# RAM.net
KiCad netlist of a schematic drawn in EAGLE
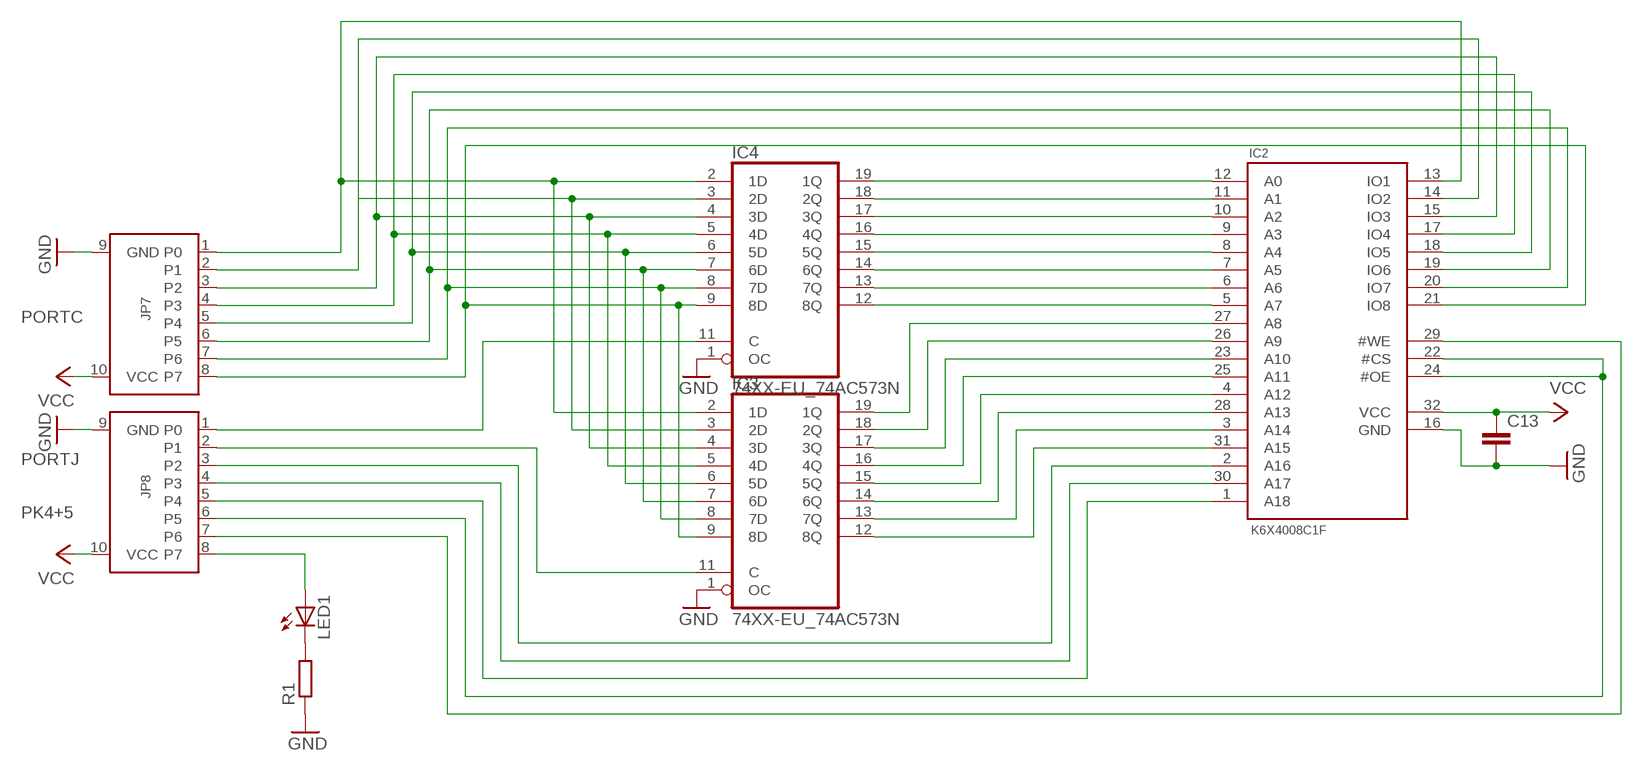
[diagram p0: schematic, sheet 1]

(export (version "E")
  (design (tool "Eeschema 10.0.6"))
  (components
    (comp (ref "C13")
      (value "C-EU050-035X075")
      (footprint "eagle-import:C050-035X075")
      (libsource (lib "eagle-import") (part "C-EU050-035X075"))
    )
    (comp (ref "IC2")
      (value "K6X4008C1F")
      (footprint "eagle-import:DIP32")
      (libsource (lib "eagle-import") (part "K6X4008C1F"))
    )
    (comp (ref "IC3")
      (value "74XX-EU_74AC573N")
      (footprint "eagle-import:74XX-EU_DIL20")
      (libsource (lib "eagle-import") (part "74XX-EU_74573NAC"))
    )
    (comp (ref "IC4")
      (value "74XX-EU_74AC573N")
      (footprint "eagle-import:74XX-EU_DIL20")
      (libsource (lib "eagle-import") (part "74XX-EU_74573NAC"))
    )
    (comp (ref "JP7")
      (value "0-ROBOTERNETZ-DEFINITIONEN_PORT")
      (footprint "eagle-import:0-ROBOTERNETZ-DEFINITIONEN_ML10")
      (libsource (lib "eagle-import") (part "0-ROBOTERNETZ-DEFINITIONEN_PORT"))
    )
    (comp (ref "JP8")
      (value "0-ROBOTERNETZ-DEFINITIONEN_PORT")
      (footprint "eagle-import:0-ROBOTERNETZ-DEFINITIONEN_ML10")
      (libsource (lib "eagle-import") (part "0-ROBOTERNETZ-DEFINITIONEN_PORT"))
    )
    (comp (ref "LED1")
      (value "LED5MM")
      (footprint "eagle-import:LED5MM")
      (libsource (lib "eagle-import") (part "LED5MM"))
    )
    (comp (ref "R1")
      (value "R-EU_0207/10")
      (footprint "eagle-import:0207_10")
      (libsource (lib "eagle-import") (part "R-EU_0207/10"))
    )
  )
  (nets
    (net (code "1") (name "GND") (class "Default")
      (node (ref "C13") (pin "2") (pinfunction "2_2") (pintype "passive"))
      (node (ref "IC2") (pin "16") (pinfunction "GND_16") (pintype "power_in"))
      (node (ref "IC3") (pin "1") (pinfunction "OC_1") (pintype "input"))
      (node (ref "IC4") (pin "1") (pinfunction "OC_1") (pintype "input"))
      (node (ref "JP7") (pin "9") (pinfunction "GND_9") (pintype "power_in"))
      (node (ref "JP8") (pin "9") (pinfunction "GND_9") (pintype "power_in"))
      (node (ref "R1") (pin "1") (pinfunction "1_1") (pintype "passive"))
    )
    (net (code "2") (name "Net-(IC2-#CS)") (class "Default")
      (node (ref "IC2") (pin "22") (pinfunction "#CS_22") (pintype "bidirectional"))
      (node (ref "IC2") (pin "24") (pinfunction "#OE_24") (pintype "bidirectional"))
      (node (ref "JP8") (pin "6") (pinfunction "P5_6") (pintype "bidirectional"))
    )
    (net (code "3") (name "Net-(IC2-#WE)") (class "Default")
      (node (ref "IC2") (pin "29") (pinfunction "#WE_29") (pintype "bidirectional"))
      (node (ref "JP8") (pin "7") (pinfunction "P6_7") (pintype "bidirectional"))
    )
    (net (code "4") (name "Net-(IC2-A0)") (class "Default")
      (node (ref "IC2") (pin "12") (pinfunction "A0_12") (pintype "bidirectional"))
      (node (ref "IC4") (pin "19") (pinfunction "1Q_19") (pintype "tri_state"))
    )
    (net (code "5") (name "Net-(IC2-A1)") (class "Default")
      (node (ref "IC2") (pin "11") (pinfunction "A1_11") (pintype "bidirectional"))
      (node (ref "IC4") (pin "18") (pinfunction "2Q_18") (pintype "tri_state"))
    )
    (net (code "6") (name "Net-(IC2-A2)") (class "Default")
      (node (ref "IC2") (pin "10") (pinfunction "A2_10") (pintype "bidirectional"))
      (node (ref "IC4") (pin "17") (pinfunction "3Q_17") (pintype "tri_state"))
    )
    (net (code "7") (name "Net-(IC2-A3)") (class "Default")
      (node (ref "IC2") (pin "9") (pinfunction "A3_9") (pintype "bidirectional"))
      (node (ref "IC4") (pin "16") (pinfunction "4Q_16") (pintype "tri_state"))
    )
    (net (code "8") (name "Net-(IC2-A4)") (class "Default")
      (node (ref "IC2") (pin "8") (pinfunction "A4_8") (pintype "bidirectional"))
      (node (ref "IC4") (pin "15") (pinfunction "5Q_15") (pintype "tri_state"))
    )
    (net (code "9") (name "Net-(IC2-A5)") (class "Default")
      (node (ref "IC2") (pin "7") (pinfunction "A5_7") (pintype "bidirectional"))
      (node (ref "IC4") (pin "14") (pinfunction "6Q_14") (pintype "tri_state"))
    )
    (net (code "10") (name "Net-(IC2-A6)") (class "Default")
      (node (ref "IC2") (pin "6") (pinfunction "A6_6") (pintype "bidirectional"))
      (node (ref "IC4") (pin "13") (pinfunction "7Q_13") (pintype "tri_state"))
    )
    (net (code "11") (name "Net-(IC2-A7)") (class "Default")
      (node (ref "IC2") (pin "5") (pinfunction "A7_5") (pintype "bidirectional"))
      (node (ref "IC4") (pin "12") (pinfunction "8Q_12") (pintype "tri_state"))
    )
    (net (code "12") (name "Net-(IC2-A8)") (class "Default")
      (node (ref "IC2") (pin "27") (pinfunction "A8_27") (pintype "bidirectional"))
      (node (ref "IC3") (pin "19") (pinfunction "1Q_19") (pintype "tri_state"))
    )
    (net (code "13") (name "Net-(IC2-A9)") (class "Default")
      (node (ref "IC2") (pin "26") (pinfunction "A9_26") (pintype "bidirectional"))
      (node (ref "IC3") (pin "18") (pinfunction "2Q_18") (pintype "tri_state"))
    )
    (net (code "14") (name "Net-(IC2-A10)") (class "Default")
      (node (ref "IC2") (pin "23") (pinfunction "A10_23") (pintype "bidirectional"))
      (node (ref "IC3") (pin "17") (pinfunction "3Q_17") (pintype "tri_state"))
    )
    (net (code "15") (name "Net-(IC2-A11)") (class "Default")
      (node (ref "IC2") (pin "25") (pinfunction "A11_25") (pintype "bidirectional"))
      (node (ref "IC3") (pin "16") (pinfunction "4Q_16") (pintype "tri_state"))
    )
    (net (code "16") (name "Net-(IC2-A12)") (class "Default")
      (node (ref "IC2") (pin "4") (pinfunction "A12_4") (pintype "bidirectional"))
      (node (ref "IC3") (pin "15") (pinfunction "5Q_15") (pintype "tri_state"))
    )
    (net (code "17") (name "Net-(IC2-A13)") (class "Default")
      (node (ref "IC2") (pin "28") (pinfunction "A13_28") (pintype "bidirectional"))
      (node (ref "IC3") (pin "14") (pinfunction "6Q_14") (pintype "tri_state"))
    )
    (net (code "18") (name "Net-(IC2-A14)") (class "Default")
      (node (ref "IC2") (pin "3") (pinfunction "A14_3") (pintype "bidirectional"))
      (node (ref "IC3") (pin "13") (pinfunction "7Q_13") (pintype "tri_state"))
    )
    (net (code "19") (name "Net-(IC2-A15)") (class "Default")
      (node (ref "IC2") (pin "31") (pinfunction "A15_31") (pintype "bidirectional"))
      (node (ref "IC3") (pin "12") (pinfunction "8Q_12") (pintype "tri_state"))
    )
    (net (code "20") (name "Net-(IC2-A16)") (class "Default")
      (node (ref "IC2") (pin "2") (pinfunction "A16_2") (pintype "bidirectional"))
      (node (ref "JP8") (pin "3") (pinfunction "P2_3") (pintype "bidirectional"))
    )
    (net (code "21") (name "Net-(IC2-A17)") (class "Default")
      (node (ref "IC2") (pin "30") (pinfunction "A17_30") (pintype "bidirectional"))
      (node (ref "JP8") (pin "4") (pinfunction "P3_4") (pintype "bidirectional"))
    )
    (net (code "22") (name "Net-(IC2-A18)") (class "Default")
      (node (ref "IC2") (pin "1") (pinfunction "A18_1") (pintype "bidirectional"))
      (node (ref "JP8") (pin "5") (pinfunction "P4_5") (pintype "bidirectional"))
    )
    (net (code "23") (name "Net-(IC2-IO1)") (class "Default")
      (node (ref "IC2") (pin "13") (pinfunction "IO1_13") (pintype "bidirectional"))
      (node (ref "IC3") (pin "2") (pinfunction "1D_2") (pintype "input"))
      (node (ref "IC4") (pin "2") (pinfunction "1D_2") (pintype "input"))
      (node (ref "JP7") (pin "1") (pinfunction "P0_1") (pintype "bidirectional"))
    )
    (net (code "24") (name "Net-(IC2-IO2)") (class "Default")
      (node (ref "IC2") (pin "14") (pinfunction "IO2_14") (pintype "bidirectional"))
      (node (ref "IC3") (pin "3") (pinfunction "2D_3") (pintype "input"))
      (node (ref "IC4") (pin "3") (pinfunction "2D_3") (pintype "input"))
      (node (ref "JP7") (pin "2") (pinfunction "P1_2") (pintype "bidirectional"))
    )
    (net (code "25") (name "Net-(IC2-IO3)") (class "Default")
      (node (ref "IC2") (pin "15") (pinfunction "IO3_15") (pintype "bidirectional"))
      (node (ref "IC3") (pin "4") (pinfunction "3D_4") (pintype "input"))
      (node (ref "IC4") (pin "4") (pinfunction "3D_4") (pintype "input"))
      (node (ref "JP7") (pin "3") (pinfunction "P2_3") (pintype "bidirectional"))
    )
    (net (code "26") (name "Net-(IC2-IO4)") (class "Default")
      (node (ref "IC2") (pin "17") (pinfunction "IO4_17") (pintype "bidirectional"))
      (node (ref "IC3") (pin "5") (pinfunction "4D_5") (pintype "input"))
      (node (ref "IC4") (pin "5") (pinfunction "4D_5") (pintype "input"))
      (node (ref "JP7") (pin "4") (pinfunction "P3_4") (pintype "bidirectional"))
    )
    (net (code "27") (name "Net-(IC2-IO5)") (class "Default")
      (node (ref "IC2") (pin "18") (pinfunction "IO5_18") (pintype "bidirectional"))
      (node (ref "IC3") (pin "6") (pinfunction "5D_6") (pintype "input"))
      (node (ref "IC4") (pin "6") (pinfunction "5D_6") (pintype "input"))
      (node (ref "JP7") (pin "5") (pinfunction "P4_5") (pintype "bidirectional"))
    )
    (net (code "28") (name "Net-(IC2-IO6)") (class "Default")
      (node (ref "IC2") (pin "19") (pinfunction "IO6_19") (pintype "bidirectional"))
      (node (ref "IC3") (pin "7") (pinfunction "6D_7") (pintype "input"))
      (node (ref "IC4") (pin "7") (pinfunction "6D_7") (pintype "input"))
      (node (ref "JP7") (pin "6") (pinfunction "P5_6") (pintype "bidirectional"))
    )
    (net (code "29") (name "Net-(IC2-IO7)") (class "Default")
      (node (ref "IC2") (pin "20") (pinfunction "IO7_20") (pintype "bidirectional"))
      (node (ref "IC3") (pin "8") (pinfunction "7D_8") (pintype "input"))
      (node (ref "IC4") (pin "8") (pinfunction "7D_8") (pintype "input"))
      (node (ref "JP7") (pin "7") (pinfunction "P6_7") (pintype "bidirectional"))
    )
    (net (code "30") (name "Net-(IC2-IO8)") (class "Default")
      (node (ref "IC2") (pin "21") (pinfunction "IO8_21") (pintype "bidirectional"))
      (node (ref "IC3") (pin "9") (pinfunction "8D_9") (pintype "input"))
      (node (ref "IC4") (pin "9") (pinfunction "8D_9") (pintype "input"))
      (node (ref "JP7") (pin "8") (pinfunction "P7_8") (pintype "bidirectional"))
    )
    (net (code "31") (name "Net-(IC3A-C)") (class "Default")
      (node (ref "IC3") (pin "11") (pinfunction "C_11") (pintype "input"))
      (node (ref "JP8") (pin "2") (pinfunction "P1_2") (pintype "bidirectional"))
    )
    (net (code "32") (name "Net-(IC4A-C)") (class "Default")
      (node (ref "IC4") (pin "11") (pinfunction "C_11") (pintype "input"))
      (node (ref "JP8") (pin "1") (pinfunction "P0_1") (pintype "bidirectional"))
    )
    (net (code "33") (name "Net-(JP8-P7)") (class "Default")
      (node (ref "JP8") (pin "8") (pinfunction "P7_8") (pintype "bidirectional"))
      (node (ref "LED1") (pin "A") (pinfunction "A_A") (pintype "passive"))
    )
    (net (code "34") (name "Net-(LED1-C)") (class "Default")
      (node (ref "LED1") (pin "K") (pinfunction "C_K") (pintype "passive"))
      (node (ref "R1") (pin "2") (pinfunction "2_2") (pintype "passive"))
    )
    (net (code "35") (name "VCC") (class "Default")
      (node (ref "C13") (pin "1") (pinfunction "1_1") (pintype "passive"))
      (node (ref "IC2") (pin "32") (pinfunction "VCC_32") (pintype "power_in"))
      (node (ref "JP7") (pin "10") (pinfunction "VCC_10") (pintype "power_in"))
      (node (ref "JP8") (pin "10") (pinfunction "VCC_10") (pintype "power_in"))
    )
  )
)
